# 02_-_Power.net
KiCad netlist of a schematic drawn in Altium Designer
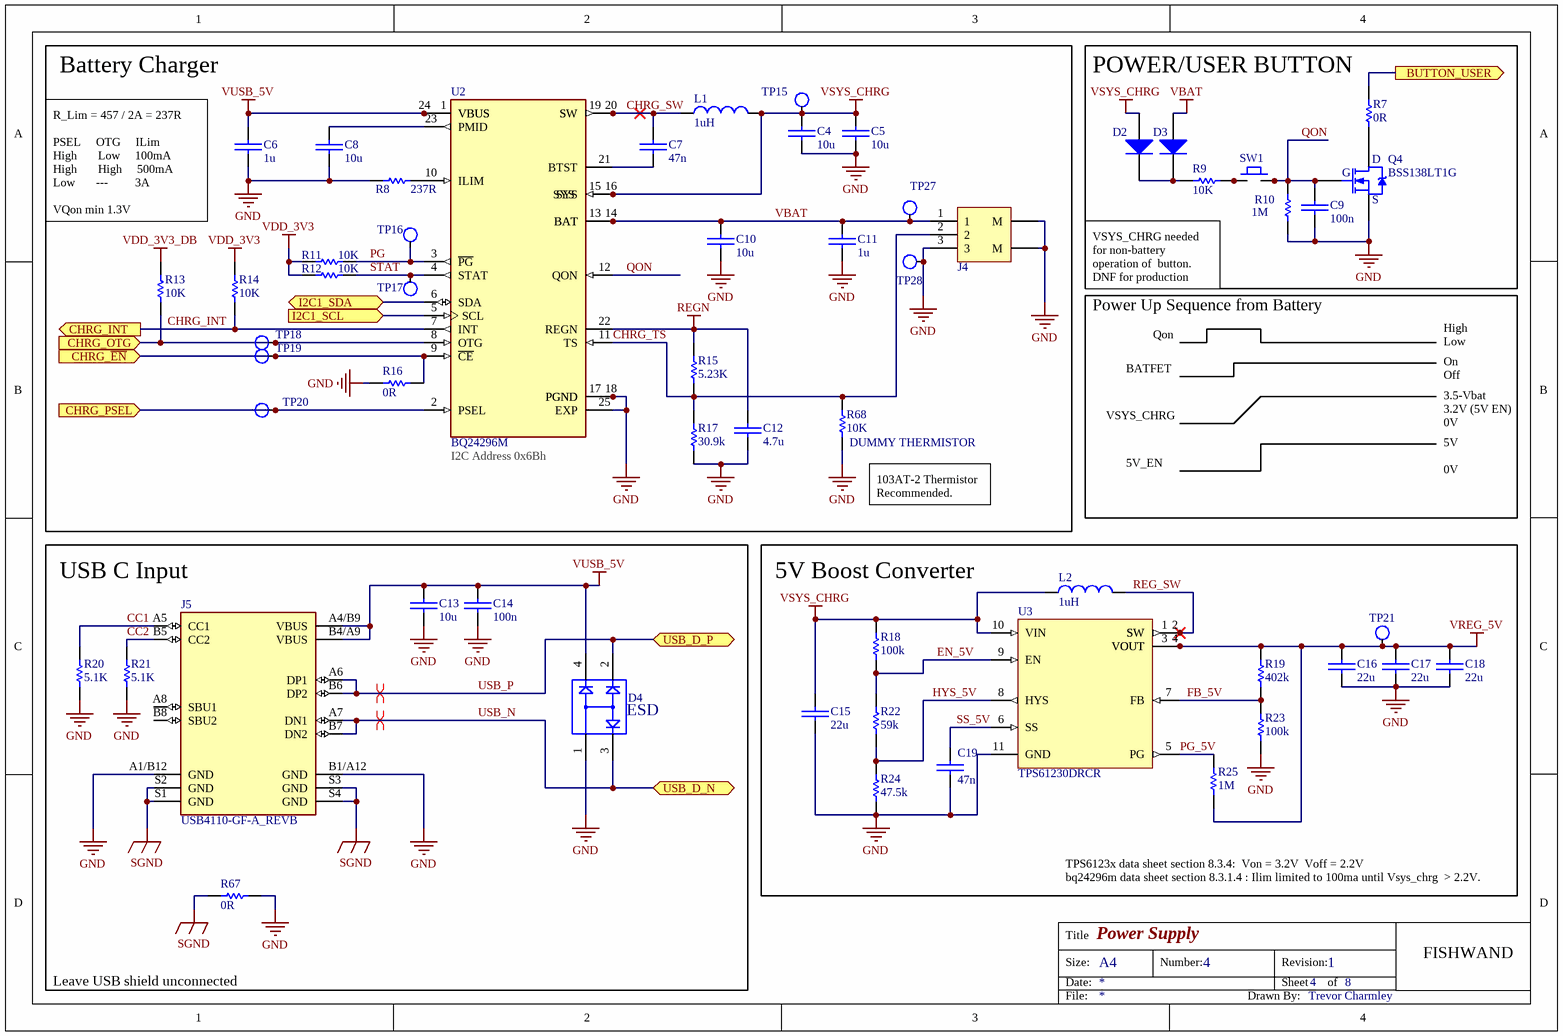
[diagram p0: 02 - Power.SchDoc]

(export (version "E")
  (design (tool "Eeschema 10.0.6"))
  (components
    (comp (ref "C4")
      (value "10u")
      (footprint "CAPC100X50X65")
      (description "CAP CER 10UF 10V X5R 0402")
      (fields (field (name "MANUFACTURER") "Samsung Electro-Mechanics"))
      (libsource (lib "FishWand_Schlib") (part "C_10UF_10V_X5R_0402"))
    )
    (comp (ref "C5")
      (value "10u")
      (footprint "CAPC100X50X65")
      (description "CAP CER 10UF 10V X5R 0402")
      (fields (field (name "MANUFACTURER") "Samsung Electro-Mechanics"))
      (libsource (lib "FishWand_Schlib") (part "C_10UF_10V_X5R_0402"))
    )
    (comp (ref "C6")
      (value "1u")
      (footprint "CAPC100X50X65")
      (description "CAP CER 1UF 25V X5R 0402")
      (fields (field (name "MANUFACTURER") "Murata Electronics North America"))
      (libsource (lib "FishWand_Schlib") (part "C_1UF_25V_X5R_0402_1"))
    )
    (comp (ref "C7")
      (value "47n")
      (footprint "CAPC100X50X65")
      (description "CAP CER 0.047UF 25V X7R 0402")
      (fields (field (name "MANUFACTURER") "Murata Electronics"))
      (libsource (lib "FishWand_Schlib") (part "C_47nF_25V_XR7_10%_0402"))
    )
    (comp (ref "C8")
      (value "10u")
      (footprint "CAPC100X50X65")
      (description "CAP CER 10UF 10V X5R 0402")
      (fields (field (name "MANUFACTURER") "Samsung Electro-Mechanics"))
      (libsource (lib "FishWand_Schlib") (part "C_10UF_10V_X5R_0402"))
    )
    (comp (ref "C9")
      (value "100n")
      (footprint "CAPC100X50X65")
      (description "CAP CER 100nF 25V X5R 0402")
      (fields (field (name "MANUFACTURER") "Murata Electronics"))
      (libsource (lib "FishWand_Schlib") (part "C_100NF_25V_X5R_0402"))
    )
    (comp (ref "C10")
      (value "10u")
      (footprint "CAPC100X50X65")
      (description "CAP CER 10UF 10V X5R 0402")
      (fields (field (name "MANUFACTURER") "Samsung Electro-Mechanics"))
      (libsource (lib "FishWand_Schlib") (part "C_10UF_10V_X5R_0402"))
    )
    (comp (ref "C11")
      (value "1u")
      (footprint "CAPC100X50X65")
      (description "CAP CER 1UF 25V X5R 0402")
      (fields (field (name "MANUFACTURER") "Murata Electronics North America"))
      (libsource (lib "FishWand_Schlib") (part "C_1UF_25V_X5R_0402_1"))
    )
    (comp (ref "C12")
      (value "4.7u")
      (footprint "CAPC100X50X65")
      (description "CAP CER 4.7UF 10V X5R 0402")
      (fields (field (name "MANUFACTURER") "Murata Electronics North America"))
      (libsource (lib "FishWand_Schlib") (part "C_4.7UF_10V_X5R_0402"))
    )
    (comp (ref "C13")
      (value "10u")
      (footprint "CAPC100X50X65")
      (description "CAP CER 10UF 10V X5R 0402")
      (fields (field (name "MANUFACTURER") "Samsung Electro-Mechanics"))
      (libsource (lib "FishWand_Schlib") (part "C_10UF_10V_X5R_0402"))
    )
    (comp (ref "C14")
      (value "100n")
      (footprint "CAPC100X50X65")
      (description "CAP CER 100nF 25V X5R 0402")
      (fields (field (name "MANUFACTURER") "Murata Electronics"))
      (libsource (lib "FishWand_Schlib") (part "C_100NF_25V_X5R_0402"))
    )
    (comp (ref "C15")
      (value "22u")
      (footprint "CAPC200X125X140L45N")
      (description "CAP CER 22UF 10V X5R 0805")
      (fields (field (name "MANUFACTURER") "Murata Electronics North America"))
      (libsource (lib "FishWand_Schlib") (part "C_22uF_10V_0805_20%"))
    )
    (comp (ref "C16")
      (value "22u")
      (footprint "CAPC200X125X140L45N")
      (description "CAP CER 22UF 10V X5R 0805")
      (fields (field (name "MANUFACTURER") "Murata Electronics North America"))
      (libsource (lib "FishWand_Schlib") (part "C_22uF_10V_0805_20%"))
    )
    (comp (ref "C17")
      (value "22u")
      (footprint "CAPC200X125X140L45N")
      (description "CAP CER 22UF 10V X5R 0805")
      (fields (field (name "MANUFACTURER") "Murata Electronics North America"))
      (libsource (lib "FishWand_Schlib") (part "C_22uF_10V_0805_20%"))
    )
    (comp (ref "C18")
      (value "22u")
      (footprint "CAPC200X125X140L45N")
      (description "CAP CER 22UF 10V X5R 0805")
      (fields (field (name "MANUFACTURER") "Murata Electronics North America"))
      (libsource (lib "FishWand_Schlib") (part "C_22uF_10V_0805_20%"))
    )
    (comp (ref "C19")
      (value "47n")
      (footprint "CAPC100X50X65")
      (description "CAP CER 0.047UF 25V X7R 0402")
      (fields (field (name "MANUFACTURER") "Murata Electronics"))
      (libsource (lib "FishWand_Schlib") (part "C_47nF_25V_XR7_10%_0402"))
    )
    (comp (ref "D2")
      (value "Diode")
      (footprint "D_SOD_323F")
      (description "DIODE GEN PURP 75V 150MA SOD323F")
      (fields (field (name "MANUFACTURER") "onsemi"))
      (libsource (lib "FishWand_Schlib") (part "D_SOD_323_75V_150mA"))
    )
    (comp (ref "D3")
      (value "Diode")
      (footprint "D_SOD_323F")
      (description "DIODE GEN PURP 75V 150MA SOD323F")
      (fields (field (name "MANUFACTURER") "onsemi"))
      (libsource (lib "FishWand_Schlib") (part "D_SOD_323_75V_150mA"))
    )
    (comp (ref "D4")
      (value "SP0503BAHTG_8.5V_TVS_DIODE")
      (footprint "FishWand_pcbLib:SOT143")
      (description "8.5V Clamp Ipp Tvs Diode Surface Mount SOT-143-4")
      (fields
        (field (name "MANUFACTURER") "Littelfuse Inc.")
        (field (name "DIGI-KEY_PART_NUMBER") "F2715CT-ND")
      )
      (libsource (lib "FishWand_Schlib") (part "SP0503BAHTG_8.5V_TVS_DIODE"))
    )
    (comp (ref "J4")
      (value "BM03B-ADHKS-GAN-ETB")
      (footprint "J_JST_BM03B-ADHKS-GAN-ETB")
      (description "CONN HEADER SMD R/A 3POS 1.3MM")
      (fields (field (name "MANUFACTURER") "JST Sales America Inc."))
      (libsource (lib "FishWand_Schlib") (part "CONN _HEADER SMD_3POS_1.3MM"))
    )
    (comp (ref "J5")
      (value "USB4110-GF-A_REVB")
      (footprint "GCT_USB4110-GF-A_REVB")
      (fields (field (name "MANUFACTURER") "GCT"))
      (libsource (lib "FishWand_Schlib") (part "USB4110-GF-A_REVB"))
    )
    (comp (ref "L1")
      (value "1uH")
      (footprint "IND1210")
      (description "1 µH Shielded Drum Core, Wirewound Inductor 5.5 A 32mOhm Max 1210 (3225 Metric)")
      (fields (field (name "MANUFACTURER") "Bourns Inc.") (field (name "TOLERANCE") "20%"))
      (libsource (lib "FishWand_Schlib") (part "L_1210_1uH_5.5A"))
    )
    (comp (ref "L2")
      (value "1uH")
      (footprint "IND1210")
      (description "1 µH Shielded Drum Core, Wirewound Inductor 5.5 A 32mOhm Max 1210 (3225 Metric)")
      (fields (field (name "MANUFACTURER") "Bourns Inc.") (field (name "TOLERANCE") "20%"))
      (libsource (lib "FishWand_Schlib") (part "L_1210_1uH_5.5A"))
    )
    (comp (ref "Q4")
      (value "BSS138LT1G")
      (footprint "SOT23-3P95_240X111L42X43N")
      (description "MOSFET N-CH 50V 200MA SOT-23")
      (fields (field (name "MANUFACTURER") "ON Semiconductor"))
      (libsource (lib "FishWand_Schlib") (part "TRANS_MOSFET_N_50V_200MA_SOT23"))
    )
    (comp (ref "R7")
      (value "0R")
      (footprint "RESC0402")
      (description "0 Ohms Jumper 0.063W, 1/16W Chip Resistor 0402 (1005 Metric) Thick Film")
      (fields (field (name "MANUFACTURER") "YAGEO") (field (name "TOLERANCE") "5%"))
      (libsource (lib "FishWand_Schlib") (part "R_0402_0R_5%"))
    )
    (comp (ref "R8")
      (value "237R")
      (footprint "RESC0402")
      (description "237 Ohms ±1% 0.063W, 1/16W Chip Resistor 0402 (1005 Metric) Moisture Resistant Thick Film")
      (fields (field (name "MANUFACTURER") "YAGEO") (field (name "TOLERANCE") "1%"))
      (libsource (lib "FishWand_Schlib") (part "R_0402_237R_1%"))
    )
    (comp (ref "R9")
      (value "10K")
      (footprint "RESC0402")
      (description "10 kOhms ±1% 0.063W, 1/16W Chip Resistor 0402 (1005 Metric) Moisture Resistant Thick Film")
      (fields (field (name "MANUFACTURER") "YAGEO") (field (name "TOLERANCE") "1%"))
      (libsource (lib "FishWand_Schlib") (part "R_0402_10K_1%"))
    )
    (comp (ref "R10")
      (value "1M")
      (footprint "RESC0402")
      (description "1 MOhms ±1% 0.063W, 1/16W Chip Resistor 0402 (1005 Metric) Moisture Resistant Thick Film")
      (fields (field (name "MANUFACTURER") "YAGEO") (field (name "TOLERANCE") "1%"))
      (libsource (lib "FishWand_Schlib") (part "R_0402_1M_1%"))
    )
    (comp (ref "R11")
      (value "10K")
      (footprint "RESC0402")
      (description "10 kOhms ±1% 0.063W, 1/16W Chip Resistor 0402 (1005 Metric) Moisture Resistant Thick Film")
      (fields (field (name "MANUFACTURER") "YAGEO") (field (name "TOLERANCE") "1%"))
      (libsource (lib "FishWand_Schlib") (part "R_0402_10K_1%"))
    )
    (comp (ref "R12")
      (value "10K")
      (footprint "RESC0402")
      (description "10 kOhms ±1% 0.063W, 1/16W Chip Resistor 0402 (1005 Metric) Moisture Resistant Thick Film")
      (fields (field (name "MANUFACTURER") "YAGEO") (field (name "TOLERANCE") "1%"))
      (libsource (lib "FishWand_Schlib") (part "R_0402_10K_1%"))
    )
    (comp (ref "R13")
      (value "10K")
      (footprint "RESC0402")
      (description "10 kOhms ±1% 0.063W, 1/16W Chip Resistor 0402 (1005 Metric) Moisture Resistant Thick Film")
      (fields (field (name "MANUFACTURER") "YAGEO") (field (name "TOLERANCE") "1%"))
      (libsource (lib "FishWand_Schlib") (part "R_0402_10K_1%"))
    )
    (comp (ref "R14")
      (value "10K")
      (footprint "RESC0402")
      (description "10 kOhms ±1% 0.063W, 1/16W Chip Resistor 0402 (1005 Metric) Moisture Resistant Thick Film")
      (fields (field (name "MANUFACTURER") "YAGEO") (field (name "TOLERANCE") "1%"))
      (libsource (lib "FishWand_Schlib") (part "R_0402_10K_1%"))
    )
    (comp (ref "R15")
      (value "5.23K")
      (footprint "RESC0402")
      (description "5.23 kOhms ±1% 0.063W, 1/16W Chip Resistor 0402 (1005 Metric) Moisture Resistant Thick Film")
      (fields (field (name "MANUFACTURER") "YAGEO") (field (name "TOLERANCE") "1%"))
      (libsource (lib "FishWand_Schlib") (part "R_0402_5.23k_1%"))
    )
    (comp (ref "R16")
      (value "0R")
      (footprint "RESC0402")
      (description "0 Ohms Jumper 0.063W, 1/16W Chip Resistor 0402 (1005 Metric) Thick Film")
      (fields (field (name "MANUFACTURER") "YAGEO") (field (name "TOLERANCE") "5%"))
      (libsource (lib "FishWand_Schlib") (part "R_0402_0R_5%"))
    )
    (comp (ref "R17")
      (value "30.9k")
      (footprint "RESC0402")
      (description "RES 30.9K OHM 1% 1/16W 0402")
      (fields (field (name "MANUFACTURER") "YAGEO") (field (name "TOLERANCE") "1%"))
      (libsource (lib "FishWand_Schlib") (part "R_0402_30.9k_1%"))
    )
    (comp (ref "R18")
      (value "100k")
      (footprint "RESC0402")
      (description "100 kOhms ±1% 0.063W, 1/16W Chip Resistor 0402 (1005 Metric) Moisture Resistant Thick Film")
      (fields (field (name "MANUFACTURER") "YAGEO") (field (name "TOLERANCE") "1%"))
      (libsource (lib "FishWand_Schlib") (part "R_0402_100k_1%"))
    )
    (comp (ref "R19")
      (value "402k")
      (footprint "RESC0402")
      (description "402 kOhms ±1% 0.063W, 1/16W Chip Resistor 0402 (1005 Metric) Moisture Resistant Thick Film")
      (fields (field (name "MANUFACTURER") "YAGEO") (field (name "TOLERANCE") "1%"))
      (libsource (lib "FishWand_Schlib") (part "R_0402_402k_1%"))
    )
    (comp (ref "R20")
      (value "5.1K")
      (footprint "RESC0402")
      (description "5.1 kOhms ±1% 0.063W, 1/16W Chip Resistor 0402 (1005 Metric) Moisture Resistant Thick Film")
      (fields (field (name "MANUFACTURER") "YAGEO") (field (name "TOLERANCE") "1%"))
      (libsource (lib "FishWand_Schlib") (part "R_0402_5.1K_1%_1"))
    )
    (comp (ref "R21")
      (value "5.1K")
      (footprint "RESC0402")
      (description "5.1 kOhms ±1% 0.063W, 1/16W Chip Resistor 0402 (1005 Metric) Moisture Resistant Thick Film")
      (fields (field (name "MANUFACTURER") "YAGEO") (field (name "TOLERANCE") "1%"))
      (libsource (lib "FishWand_Schlib") (part "R_0402_5.1K_1%_1"))
    )
    (comp (ref "R22")
      (value "59k")
      (footprint "RESC0402")
      (description "59 kOhms ±1% 0.063W, 1/16W Chip Resistor 0402 (1005 Metric) Moisture Resistant Thick Film")
      (fields (field (name "MANUFACTURER") "YAGEO"))
      (libsource (lib "FishWand_Schlib") (part "R_0402_59k_1%"))
    )
    (comp (ref "R23")
      (value "100k")
      (footprint "RESC0402")
      (description "100 kOhms ±1% 0.063W, 1/16W Chip Resistor 0402 (1005 Metric) Moisture Resistant Thick Film")
      (fields (field (name "MANUFACTURER") "YAGEO") (field (name "TOLERANCE") "1%"))
      (libsource (lib "FishWand_Schlib") (part "R_0402_100k_1%"))
    )
    (comp (ref "R24")
      (value "47.5k")
      (footprint "RESC0402")
      (description "47.5 kOhms ±1% 0.063W, 1/16W Chip Resistor 0402 (1005 Metric) Moisture Resistant Thick Film")
      (fields (field (name "MANUFACTURER") "YAGEO") (field (name "TOLERANCE") "1%"))
      (libsource (lib "FishWand_Schlib") (part "R_0402_47.5K_1%"))
    )
    (comp (ref "R25")
      (value "1M")
      (footprint "RESC0402")
      (description "1 MOhms ±1% 0.063W, 1/16W Chip Resistor 0402 (1005 Metric) Moisture Resistant Thick Film")
      (fields (field (name "MANUFACTURER") "YAGEO") (field (name "TOLERANCE") "1%"))
      (libsource (lib "FishWand_Schlib") (part "R_0402_1M_1%"))
    )
    (comp (ref "R67")
      (value "0R")
      (footprint "RESC0402")
      (description "0 Ohms Jumper 0.063W, 1/16W Chip Resistor 0402 (1005 Metric) Thick Film")
      (fields (field (name "MANUFACTURER") "YAGEO") (field (name "TOLERANCE") "5%"))
      (libsource (lib "FishWand_Schlib") (part "R_0402_0R_5%"))
    )
    (comp (ref "R68")
      (value "10K")
      (footprint "RESC0402")
      (description "10 kOhms ±1% 0.063W, 1/16W Chip Resistor 0402 (1005 Metric) Moisture Resistant Thick Film")
      (fields (field (name "MANUFACTURER") "YAGEO") (field (name "TOLERANCE") "1%"))
      (libsource (lib "FishWand_Schlib") (part "R_0402_10K_1%"))
    )
    (comp (ref "SW1")
      (value "KSC621GLFS")
      (footprint "SW_KSC621GLFS")
      (description "SWITCH_TACTILE_SPST-NO_0.05A_32V")
      (fields (field (name "MANUFACTURER") "C&K"))
      (libsource (lib "FishWand_Schlib") (part "SWITCH_TACTILE_SPST-NO_0.05A_32V"))
    )
    (comp (ref "TP15")
      (value "Test Point")
      (footprint "tp_1mm")
      (libsource (lib "FishWand_Schlib") (part "TP_1mm"))
    )
    (comp (ref "TP16")
      (value "Test Point")
      (footprint "tp_1mm")
      (libsource (lib "FishWand_Schlib") (part "TP_1mm"))
    )
    (comp (ref "TP17")
      (value "Test Point")
      (footprint "tp_1mm")
      (libsource (lib "FishWand_Schlib") (part "TP_1mm"))
    )
    (comp (ref "TP18")
      (value "Test Point")
      (footprint "tp_1mm")
      (libsource (lib "FishWand_Schlib") (part "TP_1mm"))
    )
    (comp (ref "TP19")
      (value "Test Point")
      (footprint "tp_1mm")
      (libsource (lib "FishWand_Schlib") (part "TP_1mm"))
    )
    (comp (ref "TP20")
      (value "Test Point")
      (footprint "tp_1mm")
      (libsource (lib "FishWand_Schlib") (part "TP_1mm"))
    )
    (comp (ref "TP21")
      (value "Test Point")
      (footprint "tp_1mm")
      (libsource (lib "FishWand_Schlib") (part "TP_1mm"))
    )
    (comp (ref "TP27")
      (value "Test Point")
      (footprint "tp_1mm")
      (libsource (lib "FishWand_Schlib") (part "TP_1mm"))
    )
    (comp (ref "TP28")
      (value "Test Point")
      (footprint "tp_1mm")
      (libsource (lib "FishWand_Schlib") (part "TP_1mm"))
    )
    (comp (ref "U2")
      (value "BQ24296M")
      (footprint "FishWand_pcbLib:QFN50P400X400X100-25N")
      (description "Charger IC Lithium Ion/Polymer 24-VQFN (4x4)")
      (fields (field (name "MANUFACTURER") "TI"))
      (libsource (lib "FishWand_Schlib") (part "BQ24296MRGER"))
    )
    (comp (ref "U3")
      (value "TPS61230DRCR")
      (footprint "FishWand_pcbLib:VREG_V62/16624-01YE")
      (description "High Efficiency Synchronous Boost Converter With 5-A Switch 10-VSON -40 to 85")
      (fields
        (field (name "MANUFACTURER") "Texas Instruments")
        (field (name "BUYPART") "https://www.snapeda.com/parts/TPS61230DRCR/Texas%20Instruments/view-part/51762/?ref=eda")
      )
      (libsource (lib "FishWand_Schlib") (part "U_Vreg_5V_TPS61230DRCR"))
    )
  )
  (nets
    (net (code "1") (name "/BUTTON_USER") (class "Default")
      (node (ref "R7") (pin "1") (pinfunction "1_1") (pintype "passive"))
    )
    (net (code "2") (name "/CC1") (class "Default")
      (node (ref "J5") (pin "A5") (pinfunction "CC1_A5") (pintype "bidirectional"))
      (node (ref "R20") (pin "2") (pinfunction "2_2") (pintype "passive"))
    )
    (net (code "3") (name "/CC2") (class "Default")
      (node (ref "J5") (pin "B5") (pinfunction "CC2_B5") (pintype "bidirectional"))
      (node (ref "R21") (pin "2") (pinfunction "2_2") (pintype "passive"))
    )
    (net (code "4") (name "/CHRG_INT") (class "Default")
      (node (ref "R14") (pin "1") (pinfunction "1_1") (pintype "passive"))
      (node (ref "U2") (pin "7") (pinfunction "INT_7") (pintype "output"))
    )
    (net (code "5") (name "/CHRG_OTG") (class "Default")
      (node (ref "R13") (pin "1") (pinfunction "1_1") (pintype "passive"))
      (node (ref "TP18") (pin "1") (pinfunction "1_1") (pintype "passive"))
      (node (ref "U2") (pin "8") (pinfunction "OTG_8") (pintype "input"))
    )
    (net (code "6") (name "/CHRG_PSEL") (class "Default")
      (node (ref "TP20") (pin "1") (pinfunction "1_1") (pintype "passive"))
      (node (ref "U2") (pin "2") (pinfunction "PSEL_2") (pintype "input"))
    )
    (net (code "7") (name "/CHRG_SW") (class "Default")
      (node (ref "C7") (pin "1") (pinfunction "1_1") (pintype "passive"))
      (node (ref "L1") (pin "1") (pinfunction "1_1") (pintype "passive"))
      (node (ref "U2") (pin "19") (pinfunction "SW_19") (pintype "output"))
      (node (ref "U2") (pin "20") (pinfunction "SW_20") (pintype "output"))
    )
    (net (code "8") (name "/CHRG_TS") (class "Default")
      (node (ref "J4") (pin "2") (pinfunction "2_2") (pintype "passive"))
      (node (ref "R15") (pin "1") (pinfunction "1_1") (pintype "passive"))
      (node (ref "R17") (pin "2") (pinfunction "2_2") (pintype "passive"))
      (node (ref "R68") (pin "2") (pinfunction "2_2") (pintype "passive"))
      (node (ref "U2") (pin "11") (pinfunction "TS_11") (pintype "input"))
    )
    (net (code "9") (name "/CHRG_~{EN}") (class "Default")
      (node (ref "R16") (pin "2") (pinfunction "2_2") (pintype "passive"))
      (node (ref "TP19") (pin "1") (pinfunction "1_1") (pintype "passive"))
      (node (ref "U2") (pin "9") (pinfunction "~{CE}_9") (pintype "input"))
    )
    (net (code "10") (name "/EN_5V") (class "Default")
      (node (ref "R18") (pin "1") (pinfunction "1_1") (pintype "passive"))
      (node (ref "R22") (pin "2") (pinfunction "2_2") (pintype "passive"))
      (node (ref "U3") (pin "9") (pinfunction "EN_9") (pintype "input"))
    )
    (net (code "11") (name "/FB_5V") (class "Default")
      (node (ref "R19") (pin "1") (pinfunction "1_1") (pintype "passive"))
      (node (ref "R23") (pin "2") (pinfunction "2_2") (pintype "passive"))
      (node (ref "U3") (pin "7") (pinfunction "FB_7") (pintype "input"))
    )
    (net (code "12") (name "/HYS_5V") (class "Default")
      (node (ref "R22") (pin "1") (pinfunction "1_1") (pintype "passive"))
      (node (ref "R24") (pin "2") (pinfunction "2_2") (pintype "passive"))
      (node (ref "U3") (pin "8") (pinfunction "HYS_8") (pintype "output"))
    )
    (net (code "13") (name "/I2C1_SCL") (class "Default")
      (node (ref "U2") (pin "5") (pinfunction "SCL_5") (pintype "input"))
    )
    (net (code "14") (name "/I2C1_SDA") (class "Default")
      (node (ref "U2") (pin "6") (pinfunction "SDA_6") (pintype "bidirectional"))
    )
    (net (code "15") (name "/PG") (class "Default")
      (node (ref "R11") (pin "1") (pinfunction "1_1") (pintype "passive"))
      (node (ref "TP16") (pin "1") (pinfunction "1_1") (pintype "passive"))
      (node (ref "U2") (pin "3") (pinfunction "~{PG}_3") (pintype "output"))
    )
    (net (code "16") (name "/PG_5V") (class "Default")
      (node (ref "R25") (pin "2") (pinfunction "2_2") (pintype "passive"))
      (node (ref "U3") (pin "5") (pinfunction "PG_5") (pintype "output"))
    )
    (net (code "17") (name "/QON") (class "Default")
      (node (ref "C9") (pin "1") (pinfunction "1_1") (pintype "passive"))
      (node (ref "Q4") (pin "1") (pinfunction "G_1") (pintype "passive"))
      (node (ref "R10") (pin "2") (pinfunction "2_2") (pintype "passive"))
      (node (ref "SW1") (pin "2") (pinfunction "2_2") (pintype "passive"))
      (node (ref "SW1") (pin "4") (pinfunction "4_4") (pintype "passive"))
      (node (ref "U2") (pin "12") (pinfunction "QON_12") (pintype "input"))
    )
    (net (code "18") (name "/REG_SW") (class "Default")
      (node (ref "L2") (pin "2") (pinfunction "2_2") (pintype "passive"))
      (node (ref "U3") (pin "1") (pinfunction "SW_1") (pintype "output"))
      (node (ref "U3") (pin "2") (pinfunction "SW_2") (pintype "output"))
    )
    (net (code "19") (name "/SS_5V") (class "Default")
      (node (ref "C19") (pin "1") (pinfunction "1_1") (pintype "passive"))
      (node (ref "U3") (pin "6") (pinfunction "SS_6") (pintype "input"))
    )
    (net (code "20") (name "/STAT") (class "Default")
      (node (ref "R12") (pin "1") (pinfunction "1_1") (pintype "passive"))
      (node (ref "TP17") (pin "1") (pinfunction "1_1") (pintype "passive"))
      (node (ref "U2") (pin "4") (pinfunction "STAT_4") (pintype "output"))
    )
    (net (code "21") (name "/USB_N") (class "Default")
      (node (ref "D4") (pin "3") (pinfunction "3_3") (pintype "passive"))
      (node (ref "J5") (pin "A7") (pinfunction "DN1_A7") (pintype "bidirectional"))
      (node (ref "J5") (pin "B7") (pinfunction "DN2_B7") (pintype "bidirectional"))
    )
    (net (code "22") (name "/USB_P") (class "Default")
      (node (ref "D4") (pin "2") (pinfunction "2_2") (pintype "passive"))
      (node (ref "J5") (pin "A6") (pinfunction "DP1_A6") (pintype "bidirectional"))
      (node (ref "J5") (pin "B6") (pinfunction "DP2_B6") (pintype "bidirectional"))
    )
    (net (code "23") (name "GND") (class "Default")
      (node (ref "C10") (pin "2") (pinfunction "2_2") (pintype "passive"))
      (node (ref "C11") (pin "2") (pinfunction "2_2") (pintype "passive"))
      (node (ref "C12") (pin "1") (pinfunction "1_1") (pintype "passive"))
      (node (ref "C13") (pin "2") (pinfunction "2_2") (pintype "passive"))
      (node (ref "C14") (pin "2") (pinfunction "2_2") (pintype "passive"))
      (node (ref "C15") (pin "1") (pinfunction "1_1") (pintype "passive"))
      (node (ref "C16") (pin "1") (pinfunction "1_1") (pintype "passive"))
      (node (ref "C17") (pin "1") (pinfunction "1_1") (pintype "passive"))
      (node (ref "C18") (pin "1") (pinfunction "1_1") (pintype "passive"))
      (node (ref "C19") (pin "2") (pinfunction "2_2") (pintype "passive"))
      (node (ref "C4") (pin "2") (pinfunction "2_2") (pintype "passive"))
      (node (ref "C5") (pin "2") (pinfunction "2_2") (pintype "passive"))
      (node (ref "C6") (pin "2") (pinfunction "2_2") (pintype "passive"))
      (node (ref "C8") (pin "1") (pinfunction "1_1") (pintype "passive"))
      (node (ref "C9") (pin "2") (pinfunction "2_2") (pintype "passive"))
      (node (ref "D4") (pin "1") (pinfunction "1_1") (pintype "passive"))
      (node (ref "J4") (pin "0") (pinfunction "M_0") (pintype "passive"))
      (node (ref "J4") (pin "3") (pinfunction "3_3") (pintype "passive"))
      (node (ref "J5") (pin "A1/B12") (pinfunction "GND_A1/B12") (pintype "power_in"))
      (node (ref "J5") (pin "B1/A12") (pinfunction "GND_B1/A12") (pintype "power_in"))
      (node (ref "Q4") (pin "2") (pinfunction "S_2") (pintype "passive"))
      (node (ref "R10") (pin "1") (pinfunction "1_1") (pintype "passive"))
      (node (ref "R16") (pin "1") (pinfunction "1_1") (pintype "passive"))
      (node (ref "R17") (pin "1") (pinfunction "1_1") (pintype "passive"))
      (node (ref "R20") (pin "1") (pinfunction "1_1") (pintype "passive"))
      (node (ref "R21") (pin "1") (pinfunction "1_1") (pintype "passive"))
      (node (ref "R23") (pin "1") (pinfunction "1_1") (pintype "passive"))
      (node (ref "R24") (pin "1") (pinfunction "1_1") (pintype "passive"))
      (node (ref "R67") (pin "2") (pinfunction "2_2") (pintype "passive"))
      (node (ref "R68") (pin "1") (pinfunction "1_1") (pintype "passive"))
      (node (ref "R8") (pin "1") (pinfunction "1_1") (pintype "passive"))
      (node (ref "TP28") (pin "1") (pinfunction "1_1") (pintype "passive"))
      (node (ref "U2") (pin "17") (pinfunction "PGND_17") (pintype "power_in"))
      (node (ref "U2") (pin "18") (pinfunction "PGND_18") (pintype "power_in"))
      (node (ref "U2") (pin "25") (pinfunction "EXP_25") (pintype "power_in"))
      (node (ref "U3") (pin "11") (pinfunction "GND_11") (pintype "power_in"))
    )
    (net (code "24") (name "Net-(D2-K)") (class "Default")
      (node (ref "D2") (pin "1") (pinfunction "K_1") (pintype "passive"))
      (node (ref "D3") (pin "1") (pinfunction "K_1") (pintype "passive"))
      (node (ref "R9") (pin "2") (pinfunction "2_2") (pintype "passive"))
    )
    (net (code "25") (name "Net-(Q4-D)") (class "Default")
      (node (ref "Q4") (pin "3") (pinfunction "D_3") (pintype "passive"))
      (node (ref "R7") (pin "2") (pinfunction "2_2") (pintype "passive"))
    )
    (net (code "26") (name "Net-(R9-Pad1)") (class "Default")
      (node (ref "R9") (pin "1") (pinfunction "1_1") (pintype "passive"))
      (node (ref "SW1") (pin "1") (pinfunction "1_1") (pintype "passive"))
      (node (ref "SW1") (pin "3") (pinfunction "3_3") (pintype "passive"))
    )
    (net (code "27") (name "Net-(U2-BTST)") (class "Default")
      (node (ref "C7") (pin "2") (pinfunction "2_2") (pintype "passive"))
      (node (ref "U2") (pin "21") (pinfunction "BTST_21") (pintype "power_in"))
    )
    (net (code "28") (name "Net-(U2-ILIM)") (class "Default")
      (node (ref "R8") (pin "2") (pinfunction "2_2") (pintype "passive"))
      (node (ref "U2") (pin "10") (pinfunction "ILIM_10") (pintype "input"))
    )
    (net (code "29") (name "Net-(U2-PMID)") (class "Default")
      (node (ref "C8") (pin "2") (pinfunction "2_2") (pintype "passive"))
      (node (ref "U2") (pin "23") (pinfunction "PMID_23") (pintype "output"))
    )
    (net (code "30") (name "REGN") (class "Default")
      (node (ref "C12") (pin "2") (pinfunction "2_2") (pintype "passive"))
      (node (ref "R15") (pin "2") (pinfunction "2_2") (pintype "passive"))
      (node (ref "U2") (pin "22") (pinfunction "REGN_22") (pintype "power_in"))
    )
    (net (code "31") (name "SGND") (class "Default")
      (node (ref "J5") (pin "S1") (pinfunction "GND_S1") (pintype "power_in"))
      (node (ref "J5") (pin "S2") (pinfunction "GND_S2") (pintype "power_in"))
      (node (ref "J5") (pin "S3") (pinfunction "GND_S3") (pintype "power_in"))
      (node (ref "J5") (pin "S4") (pinfunction "GND_S4") (pintype "power_in"))
      (node (ref "R67") (pin "1") (pinfunction "1_1") (pintype "passive"))
    )
    (net (code "32") (name "VBAT") (class "Default")
      (node (ref "C10") (pin "1") (pinfunction "1_1") (pintype "passive"))
      (node (ref "C11") (pin "1") (pinfunction "1_1") (pintype "passive"))
      (node (ref "D3") (pin "2") (pinfunction "A_2") (pintype "passive"))
      (node (ref "J4") (pin "1") (pinfunction "1_1") (pintype "passive"))
      (node (ref "TP27") (pin "1") (pinfunction "1_1") (pintype "passive"))
      (node (ref "U2") (pin "13") (pinfunction "BAT_13") (pintype "power_in"))
      (node (ref "U2") (pin "14") (pinfunction "BAT_14") (pintype "power_in"))
    )
    (net (code "33") (name "VDD_3V3") (class "Default")
      (node (ref "R11") (pin "2") (pinfunction "2_2") (pintype "passive"))
      (node (ref "R12") (pin "2") (pinfunction "2_2") (pintype "passive"))
      (node (ref "R14") (pin "2") (pinfunction "2_2") (pintype "passive"))
    )
    (net (code "34") (name "VDD_3V3_DB") (class "Default")
      (node (ref "R13") (pin "2") (pinfunction "2_2") (pintype "passive"))
    )
    (net (code "35") (name "VREG_5V") (class "Default")
      (node (ref "C16") (pin "2") (pinfunction "2_2") (pintype "passive"))
      (node (ref "C17") (pin "2") (pinfunction "2_2") (pintype "passive"))
      (node (ref "C18") (pin "2") (pinfunction "2_2") (pintype "passive"))
      (node (ref "R19") (pin "2") (pinfunction "2_2") (pintype "passive"))
      (node (ref "R25") (pin "1") (pinfunction "1_1") (pintype "passive"))
      (node (ref "TP21") (pin "1") (pinfunction "1_1") (pintype "passive"))
      (node (ref "U3") (pin "3") (pinfunction "VOUT_3") (pintype "power_in"))
      (node (ref "U3") (pin "4") (pinfunction "VOUT_4") (pintype "power_in"))
    )
    (net (code "36") (name "VSYS_CHRG") (class "Default")
      (node (ref "C15") (pin "2") (pinfunction "2_2") (pintype "passive"))
      (node (ref "C4") (pin "1") (pinfunction "1_1") (pintype "passive"))
      (node (ref "C5") (pin "1") (pinfunction "1_1") (pintype "passive"))
      (node (ref "D2") (pin "2") (pinfunction "A_2") (pintype "passive"))
      (node (ref "L1") (pin "2") (pinfunction "2_2") (pintype "passive"))
      (node (ref "L2") (pin "1") (pinfunction "1_1") (pintype "passive"))
      (node (ref "R18") (pin "2") (pinfunction "2_2") (pintype "passive"))
      (node (ref "TP15") (pin "1") (pinfunction "1_1") (pintype "passive"))
      (node (ref "U2") (pin "15") (pinfunction "SYS_15") (pintype "input"))
      (node (ref "U2") (pin "16") (pinfunction "SYS_16") (pintype "input"))
      (node (ref "U3") (pin "10") (pinfunction "VIN_10") (pintype "input"))
    )
    (net (code "37") (name "VUSB_5V") (class "Default")
      (node (ref "C13") (pin "1") (pinfunction "1_1") (pintype "passive"))
      (node (ref "C14") (pin "1") (pinfunction "1_1") (pintype "passive"))
      (node (ref "C6") (pin "1") (pinfunction "1_1") (pintype "passive"))
      (node (ref "D4") (pin "4") (pinfunction "4_4") (pintype "passive"))
      (node (ref "J5") (pin "A4/B9") (pinfunction "VBUS_A4/B9") (pintype "power_in"))
      (node (ref "J5") (pin "B4/A9") (pinfunction "VBUS_B4/A9") (pintype "power_in"))
      (node (ref "U2") (pin "1") (pinfunction "VBUS_1") (pintype "power_in"))
      (node (ref "U2") (pin "24") (pinfunction "VBUS_24") (pintype "power_in"))
    )
    (net (code "38") (name "unconnected-(J5-SBU1-PadA8)") (class "Default")
      (node (ref "J5") (pin "A8") (pinfunction "SBU1_A8") (pintype "bidirectional"))
    )
    (net (code "39") (name "unconnected-(J5-SBU2-PadB8)") (class "Default")
      (node (ref "J5") (pin "B8") (pinfunction "SBU2_B8") (pintype "bidirectional"))
    )
  )
)
